# Sheet1.net
KiCad netlist of a schematic drawn in Altium Designer
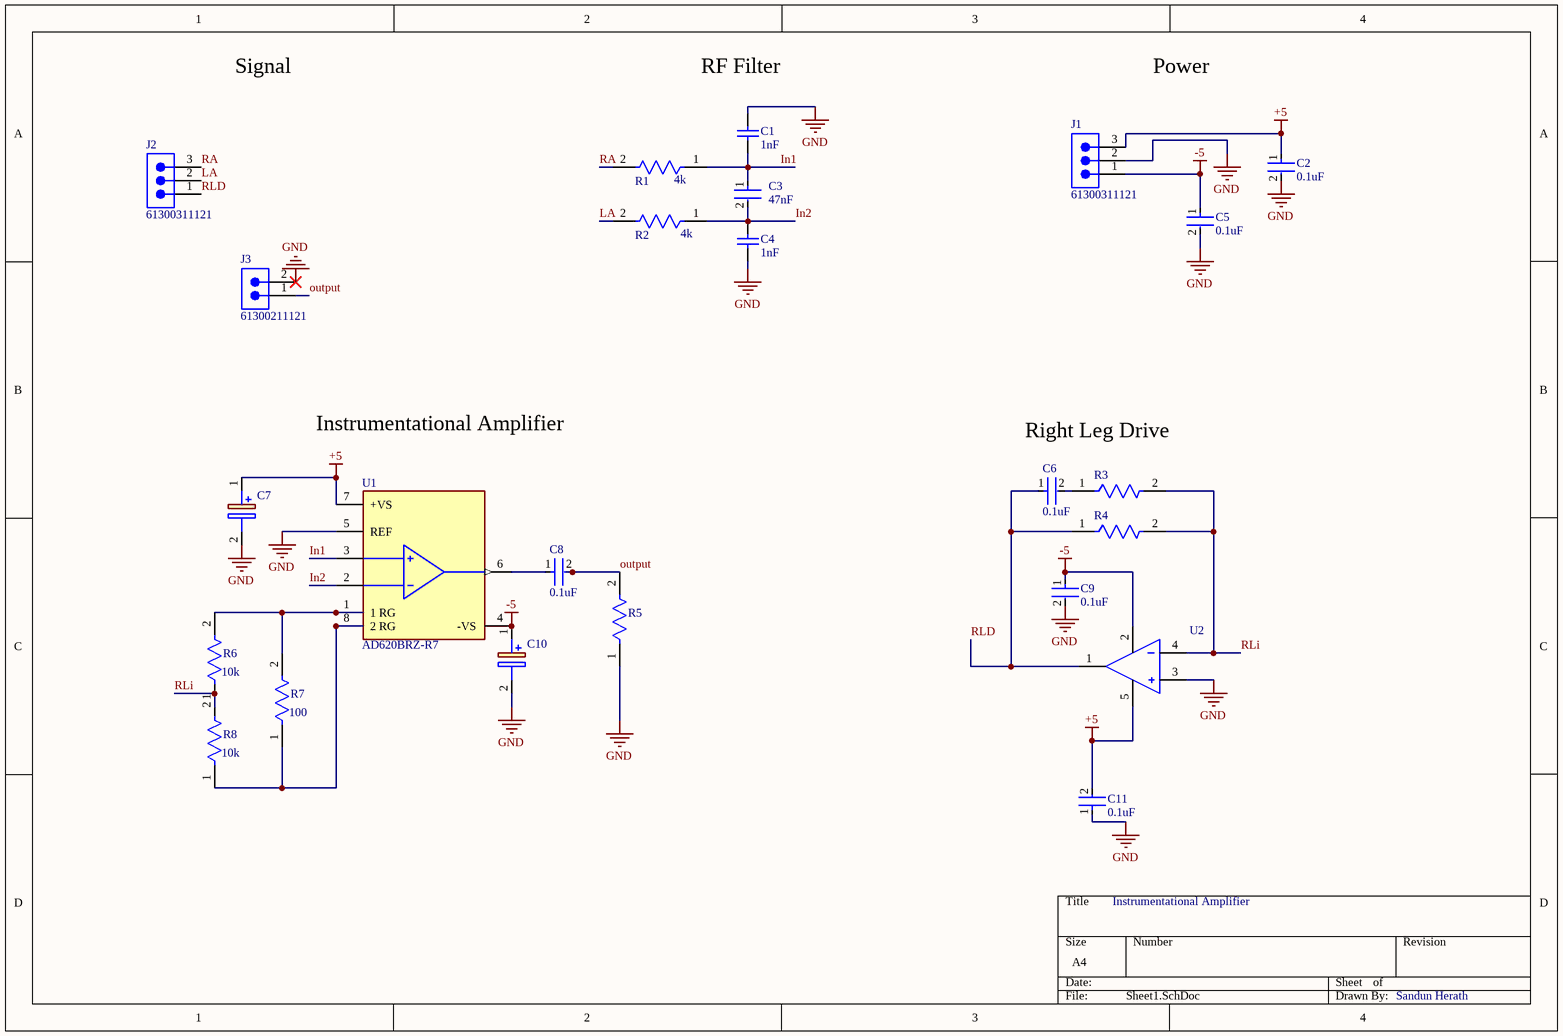
[diagram p0: Sheet1.SchDoc]

(export (version "E")
  (design (tool "Eeschema 10.0.6"))
  (components
    (comp (ref "C1")
      (value "1nF")
      (footprint "CAPC0805(2012)145_L")
      (description "CAP 1nF 50V ±5% 0805 (2012 Metric) Thickness 1.45mm SMD")
      (fields (field (name "TOLERANCE") "Â±5%"))
      (libsource (lib "Altium Content Vault") (part "CAP"))
    )
    (comp (ref "C2")
      (value "0.1uF")
      (footprint "FP-CL21-IPC_A")
      (description "CL21 Series 0805 100nF 25V ±20% Tolerance X7R Multilayer Ceramic Chip Capacitor, CL21B104MACNNNC")
      (fields (field (name "TOLERANCE") "20%"))
      (libsource (lib "Altium Content Vault") (part "b4654b650e69147ec39a6b967a45e02"))
    )
    (comp (ref "C3")
      (value "47nF")
      (footprint "FP-GRM21B-0_1-IPC_C")
      (fields (field (name "TOLERANCE") "5%"))
      (libsource (lib "Altium Content Vault") (part "b4654b650e69147ec39a6b967a45e02"))
    )
    (comp (ref "C4")
      (value "1nF")
      (footprint "CAPC0805(2012)145_L")
      (description "CAP 1nF 50V ±5% 0805 (2012 Metric) Thickness 1.45mm SMD")
      (fields (field (name "TOLERANCE") "Â±5%"))
      (libsource (lib "Altium Content Vault") (part "CAP"))
    )
    (comp (ref "C5")
      (value "0.1uF")
      (footprint "FP-CL21-IPC_A")
      (description "CL21 Series 0805 100nF 25V ±20% Tolerance X7R Multilayer Ceramic Chip Capacitor, CL21B104MACNNNC")
      (fields (field (name "TOLERANCE") "20%"))
      (libsource (lib "Altium Content Vault") (part "b4654b650e69147ec39a6b967a45e02"))
    )
    (comp (ref "C6")
      (value "0.1uF")
      (footprint "FP-CL21-IPC_A")
      (description "CL21 Series 0805 100nF 25V ±20% Tolerance X7R Multilayer Ceramic Chip Capacitor, CL21B104MACNNNC")
      (fields (field (name "TOLERANCE") "20%"))
      (libsource (lib "Altium Content Vault") (part "b4654b650e69147ec39a6b967a45e02"))
    )
    (comp (ref "C7")
      (value "593D106X96R3A2TE3")
      (footprint "SamacSys:CAPPM3216X180N")
      (description "Capacitor Polarised")
      (libsource (lib "*") (part "593D106X96R3A2TE3"))
    )
    (comp (ref "C8")
      (value "0.1uF")
      (footprint "FP-CL21-IPC_A")
      (description "CL21 Series 0805 100nF 25V ±20% Tolerance X7R Multilayer Ceramic Chip Capacitor, CL21B104MACNNNC")
      (fields (field (name "TOLERANCE") "20%"))
      (libsource (lib "Altium Content Vault") (part "b4654b650e69147ec39a6b967a45e02"))
    )
    (comp (ref "C9")
      (value "0.1uF")
      (footprint "FP-CL21-IPC_A")
      (description "CL21 Series 0805 100nF 25V ±20% Tolerance X7R Multilayer Ceramic Chip Capacitor, CL21B104MACNNNC")
      (fields (field (name "TOLERANCE") "20%"))
      (libsource (lib "Altium Content Vault") (part "b4654b650e69147ec39a6b967a45e02"))
    )
    (comp (ref "C10")
      (value "593D106X96R3A2TE3")
      (footprint "SamacSys:CAPPM3216X180N")
      (description "Capacitor Polarised")
      (libsource (lib "*") (part "593D106X96R3A2TE3"))
    )
    (comp (ref "C11")
      (value "0.1uF")
      (footprint "FP-CL21-IPC_A")
      (description "CL21 Series 0805 100nF 25V ±20% Tolerance X7R Multilayer Ceramic Chip Capacitor, CL21B104MACNNNC")
      (fields (field (name "TOLERANCE") "20%"))
      (libsource (lib "Altium Content Vault") (part "b4654b650e69147ec39a6b967a45e02"))
    )
    (comp (ref "J1")
      (value "61300311121")
      (footprint "61300311121")
      (libsource (lib "Altium Content Vault") (part "Header_Male_1R_03P"))
    )
    (comp (ref "J2")
      (value "61300311121")
      (footprint "61300311121")
      (libsource (lib "Altium Content Vault") (part "Header_Male_1R_03P"))
    )
    (comp (ref "J3")
      (value "61300211121")
      (footprint "61300211121")
      (libsource (lib "Altium Content Vault") (part "Header_Male_1R_02P"))
    )
    (comp (ref "R1")
      (value "4k")
      (footprint "FP-ERA6A-IPC_C")
      (description "RES 1K OHM 0.1% 1/8W 0805,  ERA6AEB102V")
      (fields (field (name "TOLERANCE") "0.1%"))
      (libsource (lib "Altium Content Vault") (part "1029c3af85768c4190bb7ad29bc67b5"))
    )
    (comp (ref "R2")
      (value "4k")
      (footprint "FP-ERA6A-IPC_C")
      (description "RES 1K OHM 0.1% 1/8W 0805,  ERA6AEB102V")
      (fields (field (name "TOLERANCE") "0.1%"))
      (libsource (lib "Altium Content Vault") (part "1029c3af85768c4190bb7ad29bc67b5"))
    )
    (comp (ref "R3")
      (value "ERA6AEB102V")
      (footprint "FP-ERA6A-IPC_C")
      (description "RES 1K OHM 0.1% 1/8W 0805")
      (fields (field (name "TOLERANCE") "0.1%"))
      (libsource (lib "Altium Content Vault") (part "1029c3af85768c4190bb7ad29bc67b5"))
    )
    (comp (ref "R4")
      (value "ERA6AEB102V")
      (footprint "FP-ERA6A-IPC_C")
      (description "RES 1K OHM 0.1% 1/8W 0805")
      (fields (field (name "TOLERANCE") "0.1%"))
      (libsource (lib "Altium Content Vault") (part "1029c3af85768c4190bb7ad29bc67b5"))
    )
    (comp (ref "R5")
      (value "ERA6AEB102V")
      (footprint "FP-ERA6A-IPC_C")
      (description "RES 1K OHM 0.1% 1/8W 0805")
      (fields (field (name "TOLERANCE") "0.1%"))
      (libsource (lib "Altium Content Vault") (part "1029c3af85768c4190bb7ad29bc67b5"))
    )
    (comp (ref "R6")
      (value "10k")
      (footprint "FP-ERA6A-IPC_C")
      (description "RES 1K OHM 0.1% 1/8W 0805,    ERA6AEB102V")
      (fields (field (name "TOLERANCE") "0.1%"))
      (libsource (lib "Altium Content Vault") (part "1029c3af85768c4190bb7ad29bc67b5"))
    )
    (comp (ref "R7")
      (value "100")
      (footprint "FP-ERA6A-IPC_C")
      (description "RES 1K OHM 0.1% 1/8W 0805,  ERA6AEB102V")
      (fields (field (name "TOLERANCE") "0.1%"))
      (libsource (lib "Altium Content Vault") (part "1029c3af85768c4190bb7ad29bc67b5"))
    )
    (comp (ref "R8")
      (value "10k")
      (footprint "FP-ERA6A-IPC_C")
      (description "RES 1K OHM 0.1% 1/8W 0805,  ERA6AEB102V")
      (fields (field (name "TOLERANCE") "0.1%"))
      (libsource (lib "Altium Content Vault") (part "1029c3af85768c4190bb7ad29bc67b5"))
    )
    (comp (ref "U1")
      (value "AD620BRZ-R7")
      (footprint "FP-R-8-IPC_C")
      (description "IC INST AMP 1 CIRCUIT 8SOIC")
      (libsource (lib "Altium Content Vault") (part "34122d4f8c853147fd0c9ba0f33876e"))
    )
    (comp (ref "U2")
      (value "TLV9151IDBVR")
      (footprint "FP-DBV0005A-IPC_A")
      (description "OPAMP")
      (libsource (lib "Altium Content Vault") (part "bdbec92199ce4306a818faf70a0ce6e"))
    )
  )
  (nets
    (net (code "1") (name "+5") (class "Default")
      (node (ref "C11") (pin "2") (pinfunction "2_2") (pintype "passive"))
      (node (ref "C2") (pin "1") (pinfunction "1_1") (pintype "passive"))
      (node (ref "C7") (pin "1") (pinfunction "+_1") (pintype "passive"))
      (node (ref "J1") (pin "3") (pinfunction "3_3") (pintype "passive"))
      (node (ref "U1") (pin "7") (pinfunction "+VS_7") (pintype "power_in"))
      (node (ref "U2") (pin "5") (pinfunction "V+_5") (pintype "power_in"))
    )
    (net (code "2") (name "-5") (class "Default")
      (node (ref "C10") (pin "1") (pinfunction "+_1") (pintype "passive"))
      (node (ref "C5") (pin "1") (pinfunction "1_1") (pintype "passive"))
      (node (ref "C9") (pin "1") (pinfunction "1_1") (pintype "passive"))
      (node (ref "J1") (pin "1") (pinfunction "1_1") (pintype "passive"))
      (node (ref "U1") (pin "4") (pinfunction "-VS_4") (pintype "power_in"))
      (node (ref "U2") (pin "2") (pinfunction "V-_2") (pintype "power_in"))
    )
    (net (code "3") (name "/In1") (class "Default")
      (node (ref "C1") (pin "1") (pinfunction "1_1") (pintype "passive"))
      (node (ref "C3") (pin "1") (pinfunction "1_1") (pintype "passive"))
      (node (ref "R1") (pin "1") (pinfunction "1_1") (pintype "passive"))
      (node (ref "U1") (pin "3") (pinfunction "+IN_3") (pintype "tri_state"))
    )
    (net (code "4") (name "/In2") (class "Default")
      (node (ref "C3") (pin "2") (pinfunction "2_2") (pintype "passive"))
      (node (ref "C4") (pin "2") (pinfunction "2_2") (pintype "passive"))
      (node (ref "R2") (pin "1") (pinfunction "1_1") (pintype "passive"))
      (node (ref "U1") (pin "2") (pinfunction "-IN_2") (pintype "tri_state"))
    )
    (net (code "5") (name "/LA") (class "Default")
      (node (ref "J2") (pin "2") (pinfunction "2_2") (pintype "passive"))
      (node (ref "R2") (pin "2") (pinfunction "2_2") (pintype "passive"))
    )
    (net (code "6") (name "/RA") (class "Default")
      (node (ref "J2") (pin "3") (pinfunction "3_3") (pintype "passive"))
      (node (ref "R1") (pin "2") (pinfunction "2_2") (pintype "passive"))
    )
    (net (code "7") (name "/RLD") (class "Default")
      (node (ref "C6") (pin "1") (pinfunction "1_1") (pintype "passive"))
      (node (ref "J2") (pin "1") (pinfunction "1_1") (pintype "passive"))
      (node (ref "R4") (pin "1") (pinfunction "1_1") (pintype "passive"))
      (node (ref "U2") (pin "1") (pinfunction "OUT_1") (pintype "passive"))
    )
    (net (code "8") (name "/RLi") (class "Default")
      (node (ref "R3") (pin "2") (pinfunction "2_2") (pintype "passive"))
      (node (ref "R4") (pin "2") (pinfunction "2_2") (pintype "passive"))
      (node (ref "R6") (pin "1") (pinfunction "1_1") (pintype "passive"))
      (node (ref "R8") (pin "2") (pinfunction "2_2") (pintype "passive"))
      (node (ref "U2") (pin "4") (pinfunction "IN-_4") (pintype "tri_state"))
    )
    (net (code "9") (name "/output") (class "Default")
      (node (ref "C8") (pin "2") (pinfunction "2_2") (pintype "passive"))
      (node (ref "J3") (pin "1") (pinfunction "1_1") (pintype "passive"))
      (node (ref "R5") (pin "2") (pinfunction "2_2") (pintype "passive"))
    )
    (net (code "10") (name "GND") (class "Default")
      (node (ref "C1") (pin "2") (pinfunction "2_2") (pintype "passive"))
      (node (ref "C10") (pin "2") (pinfunction "-_2") (pintype "passive"))
      (node (ref "C11") (pin "1") (pinfunction "1_1") (pintype "passive"))
      (node (ref "C2") (pin "2") (pinfunction "2_2") (pintype "passive"))
      (node (ref "C4") (pin "1") (pinfunction "1_1") (pintype "passive"))
      (node (ref "C5") (pin "2") (pinfunction "2_2") (pintype "passive"))
      (node (ref "C7") (pin "2") (pinfunction "-_2") (pintype "passive"))
      (node (ref "C9") (pin "2") (pinfunction "2_2") (pintype "passive"))
      (node (ref "J1") (pin "2") (pinfunction "2_2") (pintype "passive"))
      (node (ref "J3") (pin "2") (pinfunction "2_2") (pintype "passive"))
      (node (ref "R5") (pin "1") (pinfunction "1_1") (pintype "passive"))
      (node (ref "U1") (pin "5") (pinfunction "REF_5") (pintype "passive"))
      (node (ref "U2") (pin "3") (pinfunction "IN+_3") (pintype "tri_state"))
    )
    (net (code "11") (name "Net-(C6-Pad2)") (class "Default")
      (node (ref "C6") (pin "2") (pinfunction "2_2") (pintype "passive"))
      (node (ref "R3") (pin "1") (pinfunction "1_1") (pintype "passive"))
    )
    (net (code "12") (name "Net-(U1-1_RG)") (class "Default")
      (node (ref "R6") (pin "2") (pinfunction "2_2") (pintype "passive"))
      (node (ref "R7") (pin "2") (pinfunction "2_2") (pintype "passive"))
      (node (ref "U1") (pin "1") (pinfunction "1_RG_1") (pintype "passive"))
    )
    (net (code "13") (name "Net-(U1-2_RG)") (class "Default")
      (node (ref "R7") (pin "1") (pinfunction "1_1") (pintype "passive"))
      (node (ref "R8") (pin "1") (pinfunction "1_1") (pintype "passive"))
      (node (ref "U1") (pin "8") (pinfunction "2_RG_8") (pintype "passive"))
    )
    (net (code "14") (name "Net-(U1-OUTPUT)") (class "Default")
      (node (ref "C8") (pin "1") (pinfunction "1_1") (pintype "passive"))
      (node (ref "U1") (pin "6") (pinfunction "OUTPUT_6") (pintype "output"))
    )
  )
)
